# Receive.net
KiCad netlist of a schematic drawn in Altium Designer
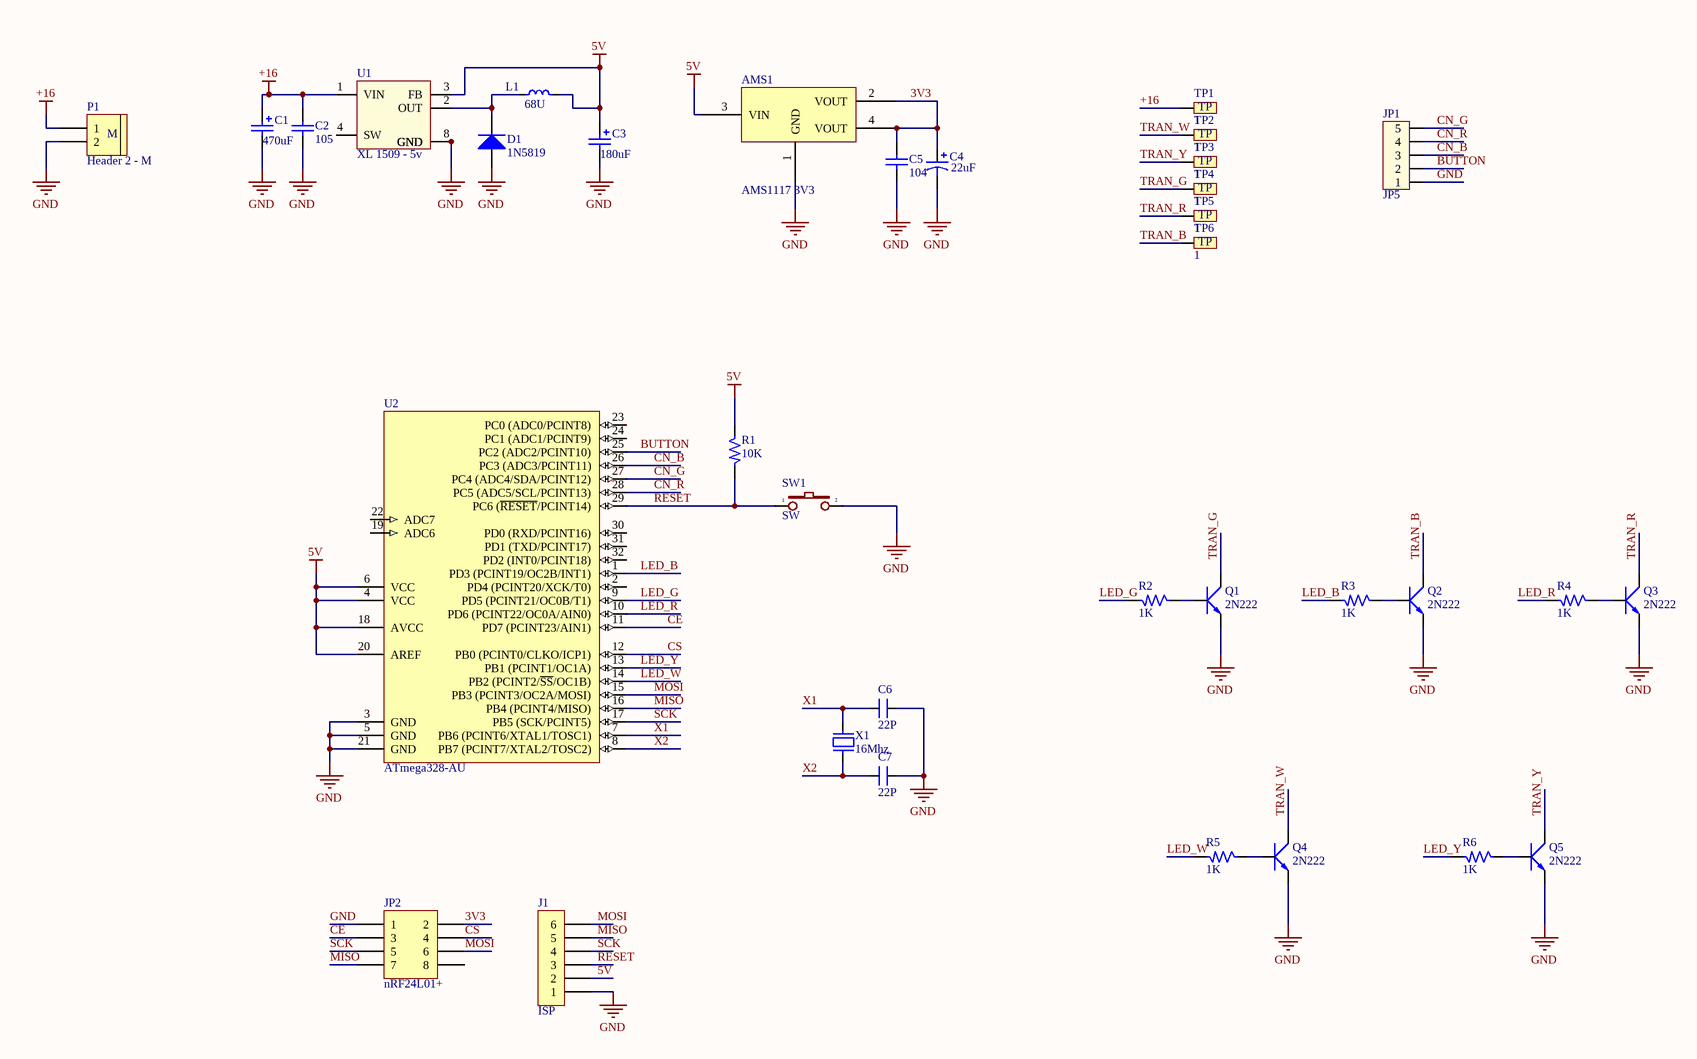
[diagram p0: Receive.SchDoc]

(export (version "E")
  (design (tool "Eeschema 10.0.6"))
  (components
    (comp (ref "AMS1")
      (value "AMS1117 3V3")
      (footprint "SOT223-4N")
      (description "AMS")
      (libsource (lib "Thu Vien Chuan") (part "AMS1117"))
    )
    (comp (ref "C1")
      (value "470uF")
      (footprint "CP2/5")
      (description "Polarized Capacitor (Surface Mount)")
      (fields (field (name "PUBLISHER") "Altium Limited"))
      (libsource (lib "Thu Vien Chuan") (part "Cap Pol3"))
    )
    (comp (ref "C2")
      (value "105")
      (footprint "Thu Vien Chuan :CN-SMD-0805")
      (libsource (lib "Thu Vien Chuan") (part "CAP 33P_0805"))
    )
    (comp (ref "C3")
      (value "180uF")
      (footprint "CP2/5")
      (description "Polarized Capacitor (Surface Mount)")
      (fields (field (name "PUBLISHER") "Altium Limited"))
      (libsource (lib "Thu Vien Chuan") (part "Cap Pol3"))
    )
    (comp (ref "C4")
      (value "22uF")
      (footprint "C5mm")
      (description "Polarized Capacitor (Axial)")
      (fields (field (name "PUBLISHER") "Altium Limited"))
      (libsource (lib "Thu Vien Chuan") (part "Cap Pol 5mm"))
    )
    (comp (ref "C5")
      (value "104")
      (footprint "Thu Vien Chuan :CN-SMD-0805")
      (libsource (lib "Thu Vien Chuan") (part "CAP 33P_0805"))
    )
    (comp (ref "C6")
      (value "22P")
      (footprint "Thu Vien Chuan :CN-SMD-0805")
      (description "Cap np  1pF - 472pF")
      (libsource (lib "Thu Vien Chuan") (part "CN1"))
    )
    (comp (ref "C7")
      (value "22P")
      (footprint "Thu Vien Chuan :CN-SMD-0805")
      (description "Cap np  1pF - 472pF")
      (libsource (lib "Thu Vien Chuan") (part "CN1"))
    )
    (comp (ref "D1")
      (value "1N5819")
      (footprint "HueNguyenLib:SS14")
      (libsource (lib "Thu Vien Chuan") (part "1N5819"))
    )
    (comp (ref "J1")
      (value "ISP")
      (footprint "Thu Vien Chuan :Header6")
      (description "JUMP DON DUC 2.54")
      (libsource (lib "Thu Vien Chuan") (part "JUMP 6"))
    )
    (comp (ref "JP1")
      (value "JP5")
      (footprint "XH2.54-5P")
      (description "Connector 5")
      (libsource (lib "Thu Vien Chuan") (part "Header 5P"))
    )
    (comp (ref "JP2")
      (value "nRF24L01+")
      (footprint "HDR2X4")
      (description "JUMP DOI DUC")
      (fields (field (name "PUBLISHER") "Altium Limited"))
      (libsource (lib "Thu Vien Chuan") (part "JUMP DOI-4"))
    )
    (comp (ref "L1")
      (value "68U")
      (footprint "HueNguyenLib:CD75")
      (description "Cuon cam")
      (libsource (lib "Thu Vien Chuan") (part "L100uH3A"))
    )
    (comp (ref "P1")
      (value "Header 2 - M")
      (footprint "Medium - Header 2")
      (description "Header, 2-Pin, Medium")
      (fields (field (name "PUBLISHER") "Altium Limited"))
      (libsource (lib "Thu Vien Chuan") (part "Header 2 - M"))
    )
    (comp (ref "Q1")
      (value "2N222")
      (footprint "Thu Vien Chuan :SOT23-231")
      (description "P 600mW, EBC")
      (libsource (lib "Thu Vien Chuan") (part "NPN_EBC"))
    )
    (comp (ref "Q2")
      (value "2N222")
      (footprint "Thu Vien Chuan :SOT23-231")
      (description "P 600mW, EBC")
      (libsource (lib "Thu Vien Chuan") (part "NPN_EBC"))
    )
    (comp (ref "Q3")
      (value "2N222")
      (footprint "Thu Vien Chuan :SOT23-231")
      (description "P 600mW, EBC")
      (libsource (lib "Thu Vien Chuan") (part "NPN_EBC"))
    )
    (comp (ref "Q4")
      (value "2N222")
      (footprint "Thu Vien Chuan :SOT23-231")
      (description "P 600mW, EBC")
      (libsource (lib "Thu Vien Chuan") (part "NPN_EBC"))
    )
    (comp (ref "Q5")
      (value "2N222")
      (footprint "Thu Vien Chuan :SOT23-231")
      (description "P 600mW, EBC")
      (libsource (lib "Thu Vien Chuan") (part "NPN_EBC"))
    )
    (comp (ref "R1")
      (value "10K")
      (footprint "Thu Vien Chuan :RES-SMD-0805")
      (description "Tro 1/4W")
      (libsource (lib "Thu Vien Chuan") (part "RES 1/4W"))
    )
    (comp (ref "R2")
      (value "1K")
      (footprint "Thu Vien Chuan :RES-SMD-0805")
      (description "Tro 1/4W")
      (libsource (lib "Thu Vien Chuan") (part "RES 1/4W"))
    )
    (comp (ref "R3")
      (value "1K")
      (footprint "Thu Vien Chuan :RES-SMD-0805")
      (description "Tro 1/4W")
      (libsource (lib "Thu Vien Chuan") (part "RES 1/4W"))
    )
    (comp (ref "R4")
      (value "1K")
      (footprint "Thu Vien Chuan :RES-SMD-0805")
      (description "Tro 1/4W")
      (libsource (lib "Thu Vien Chuan") (part "RES 1/4W"))
    )
    (comp (ref "R5")
      (value "1K")
      (footprint "Thu Vien Chuan :RES-SMD-0805")
      (description "Tro 1/4W")
      (libsource (lib "Thu Vien Chuan") (part "RES 1/4W"))
    )
    (comp (ref "R6")
      (value "1K")
      (footprint "Thu Vien Chuan :RES-SMD-0805")
      (description "Tro 1/4W")
      (libsource (lib "Thu Vien Chuan") (part "RES 1/4W"))
    )
    (comp (ref "SW1")
      (value "SW")
      (footprint "SW2")
      (description "Switch button 2 pin")
      (libsource (lib "Thu Vien Chuan") (part "SW2"))
    )
    (comp (ref "TP1")
      (value "1")
      (footprint "TP")
      (description "CONNECT 1")
      (libsource (lib "Thu Vien Chuan") (part "TP"))
    )
    (comp (ref "TP2")
      (value "1")
      (footprint "TP")
      (description "CONNECT 1")
      (libsource (lib "Thu Vien Chuan") (part "TP"))
    )
    (comp (ref "TP3")
      (value "1")
      (footprint "TP")
      (description "CONNECT 1")
      (libsource (lib "Thu Vien Chuan") (part "TP"))
    )
    (comp (ref "TP4")
      (value "1")
      (footprint "TP")
      (description "CONNECT 1")
      (libsource (lib "Thu Vien Chuan") (part "TP"))
    )
    (comp (ref "TP5")
      (value "1")
      (footprint "TP")
      (description "CONNECT 1")
      (libsource (lib "Thu Vien Chuan") (part "TP"))
    )
    (comp (ref "TP6")
      (value "1")
      (footprint "TP")
      (description "CONNECT 1")
      (libsource (lib "Thu Vien Chuan") (part "TP"))
    )
    (comp (ref "U1")
      (value "XL 1509 - 5v")
      (footprint "HueNguyenLib:XL1509 - SOIC 8")
      (description "IC HA AP 5V")
      (libsource (lib "HueNguyenLib") (part "XL 1509 - 5v"))
    )
    (comp (ref "U2")
      (value "ATmega328-AU")
      (footprint "TQFP32")
      (fields (field (name "PUBLISHER") "Altium Limited"))
      (libsource (lib "Thu Vien Chuan") (part "ATmega328-AU"))
    )
    (comp (ref "X1")
      (value "16Mhz")
      (footprint "XT2")
      (description "Crystal For all Crystal 2pin.")
      (libsource (lib "Thu Vien Chuan") (part "XT2"))
    )
  )
  (nets
    (net (code "1") (name "+16") (class "Default")
      (node (ref "C1") (pin "1") (pinfunction "1_1") (pintype "passive"))
      (node (ref "C2") (pin "2") (pinfunction "2_2") (pintype "passive"))
      (node (ref "P1") (pin "1") (pinfunction "1_1") (pintype "passive"))
      (node (ref "TP1") (pin "TP1") (pinfunction "0_TP1") (pintype "passive"))
      (node (ref "U1") (pin "1") (pinfunction "VIN_1") (pintype "passive"))
    )
    (net (code "2") (name "/3V3") (class "Default")
      (node (ref "AMS1") (pin "2") (pinfunction "VOUT_2") (pintype "passive"))
      (node (ref "AMS1") (pin "4") (pinfunction "VOUT_4") (pintype "passive"))
      (node (ref "C4") (pin "1") (pinfunction "1_1") (pintype "passive"))
      (node (ref "C5") (pin "2") (pinfunction "2_2") (pintype "passive"))
      (node (ref "JP2") (pin "2") (pinfunction "2_2") (pintype "passive"))
    )
    (net (code "3") (name "/BUTTON") (class "Default")
      (node (ref "JP1") (pin "2") (pinfunction "2_2") (pintype "passive"))
      (node (ref "U2") (pin "25") (pinfunction "PC2_(ADC2/PCINT10)_25") (pintype "bidirectional"))
    )
    (net (code "4") (name "/CE") (class "Default")
      (node (ref "JP2") (pin "3") (pinfunction "3_3") (pintype "passive"))
      (node (ref "U2") (pin "11") (pinfunction "PD7_(PCINT23/AIN1)_11") (pintype "bidirectional"))
    )
    (net (code "5") (name "/CN_B") (class "Default")
      (node (ref "JP1") (pin "3") (pinfunction "3_3") (pintype "passive"))
      (node (ref "U2") (pin "26") (pinfunction "PC3_(ADC3/PCINT11)_26") (pintype "bidirectional"))
    )
    (net (code "6") (name "/CN_G") (class "Default")
      (node (ref "JP1") (pin "5") (pinfunction "5_5") (pintype "passive"))
      (node (ref "U2") (pin "27") (pinfunction "PC4_(ADC4/SDA/PCINT12)_27") (pintype "bidirectional"))
    )
    (net (code "7") (name "/CN_R") (class "Default")
      (node (ref "JP1") (pin "4") (pinfunction "4_4") (pintype "passive"))
      (node (ref "U2") (pin "28") (pinfunction "PC5_(ADC5/SCL/PCINT13)_28") (pintype "bidirectional"))
    )
    (net (code "8") (name "/CS") (class "Default")
      (node (ref "JP2") (pin "4") (pinfunction "4_4") (pintype "passive"))
      (node (ref "U2") (pin "12") (pinfunction "PB0_(PCINT0/CLKO/ICP1)_12") (pintype "bidirectional"))
    )
    (net (code "9") (name "/LED_B") (class "Default")
      (node (ref "R3") (pin "2") (pinfunction "2_2") (pintype "passive"))
      (node (ref "U2") (pin "1") (pinfunction "PD3_(PCINT19/OC2B/INT1)_1") (pintype "bidirectional"))
    )
    (net (code "10") (name "/LED_G") (class "Default")
      (node (ref "R2") (pin "2") (pinfunction "2_2") (pintype "passive"))
      (node (ref "U2") (pin "9") (pinfunction "PD5_(PCINT21/OC0B/T1)_9") (pintype "bidirectional"))
    )
    (net (code "11") (name "/LED_R") (class "Default")
      (node (ref "R4") (pin "2") (pinfunction "2_2") (pintype "passive"))
      (node (ref "U2") (pin "10") (pinfunction "PD6_(PCINT22/OC0A/AIN0)_10") (pintype "bidirectional"))
    )
    (net (code "12") (name "/LED_W") (class "Default")
      (node (ref "R5") (pin "2") (pinfunction "2_2") (pintype "passive"))
      (node (ref "U2") (pin "14") (pinfunction "PB2_(PCINT2/~{SS}/OC1B)_14") (pintype "bidirectional"))
    )
    (net (code "13") (name "/LED_Y") (class "Default")
      (node (ref "R6") (pin "2") (pinfunction "2_2") (pintype "passive"))
      (node (ref "U2") (pin "13") (pinfunction "PB1_(PCINT1/OC1A)_13") (pintype "bidirectional"))
    )
    (net (code "14") (name "/MISO") (class "Default")
      (node (ref "J1") (pin "5") (pinfunction "5_5") (pintype "passive"))
      (node (ref "JP2") (pin "7") (pinfunction "7_7") (pintype "passive"))
      (node (ref "U2") (pin "16") (pinfunction "PB4_(PCINT4/MISO)_16") (pintype "bidirectional"))
    )
    (net (code "15") (name "/MOSI") (class "Default")
      (node (ref "J1") (pin "6") (pinfunction "6_6") (pintype "passive"))
      (node (ref "JP2") (pin "6") (pinfunction "6_6") (pintype "passive"))
      (node (ref "U2") (pin "15") (pinfunction "PB3_(PCINT3/OC2A/MOSI)_15") (pintype "bidirectional"))
    )
    (net (code "16") (name "/RESET") (class "Default")
      (node (ref "J1") (pin "3") (pinfunction "3_3") (pintype "passive"))
      (node (ref "R1") (pin "2") (pinfunction "2_2") (pintype "passive"))
      (node (ref "SW1") (pin "1") (pinfunction "1_1") (pintype "passive"))
      (node (ref "U2") (pin "29") (pinfunction "PC6_(~{RESET}/PCINT14)_29") (pintype "bidirectional"))
    )
    (net (code "17") (name "/SCK") (class "Default")
      (node (ref "J1") (pin "4") (pinfunction "4_4") (pintype "passive"))
      (node (ref "JP2") (pin "5") (pinfunction "5_5") (pintype "passive"))
      (node (ref "U2") (pin "17") (pinfunction "PB5_(SCK/PCINT5)_17") (pintype "bidirectional"))
    )
    (net (code "18") (name "/TRAN_B") (class "Default")
      (node (ref "Q2") (pin "3") (pinfunction "C_3") (pintype "passive"))
      (node (ref "TP6") (pin "TP1") (pinfunction "0_TP1") (pintype "passive"))
    )
    (net (code "19") (name "/TRAN_G") (class "Default")
      (node (ref "Q1") (pin "3") (pinfunction "C_3") (pintype "passive"))
      (node (ref "TP4") (pin "TP1") (pinfunction "0_TP1") (pintype "passive"))
    )
    (net (code "20") (name "/TRAN_R") (class "Default")
      (node (ref "Q3") (pin "3") (pinfunction "C_3") (pintype "passive"))
      (node (ref "TP5") (pin "TP1") (pinfunction "0_TP1") (pintype "passive"))
    )
    (net (code "21") (name "/TRAN_W") (class "Default")
      (node (ref "Q4") (pin "3") (pinfunction "C_3") (pintype "passive"))
      (node (ref "TP2") (pin "TP1") (pinfunction "0_TP1") (pintype "passive"))
    )
    (net (code "22") (name "/TRAN_Y") (class "Default")
      (node (ref "Q5") (pin "3") (pinfunction "C_3") (pintype "passive"))
      (node (ref "TP3") (pin "TP1") (pinfunction "0_TP1") (pintype "passive"))
    )
    (net (code "23") (name "/X1") (class "Default")
      (node (ref "C6") (pin "2") (pinfunction "2_2") (pintype "passive"))
      (node (ref "U2") (pin "7") (pinfunction "PB6_(PCINT6/XTAL1/TOSC1)_7") (pintype "bidirectional"))
      (node (ref "X1") (pin "2") (pinfunction "2_2") (pintype "passive"))
    )
    (net (code "24") (name "/X2") (class "Default")
      (node (ref "C7") (pin "2") (pinfunction "2_2") (pintype "passive"))
      (node (ref "U2") (pin "8") (pinfunction "PB7_(PCINT7/XTAL2/TOSC2)_8") (pintype "bidirectional"))
      (node (ref "X1") (pin "1") (pinfunction "1_1") (pintype "passive"))
    )
    (net (code "25") (name "5V") (class "Default")
      (node (ref "AMS1") (pin "3") (pinfunction "VIN_3") (pintype "passive"))
      (node (ref "C3") (pin "1") (pinfunction "1_1") (pintype "passive"))
      (node (ref "J1") (pin "2") (pinfunction "2_2") (pintype "passive"))
      (node (ref "L1") (pin "2") (pinfunction "2_2") (pintype "passive"))
      (node (ref "R1") (pin "1") (pinfunction "1_1") (pintype "passive"))
      (node (ref "U1") (pin "3") (pinfunction "FB_3") (pintype "passive"))
      (node (ref "U2") (pin "18") (pinfunction "AVCC_18") (pintype "power_in"))
      (node (ref "U2") (pin "20") (pinfunction "AREF_20") (pintype "passive"))
      (node (ref "U2") (pin "4") (pinfunction "VCC_4") (pintype "power_in"))
      (node (ref "U2") (pin "6") (pinfunction "VCC_6") (pintype "power_in"))
    )
    (net (code "26") (name "GND") (class "Default")
      (node (ref "AMS1") (pin "1") (pinfunction "GND_1") (pintype "passive"))
      (node (ref "C1") (pin "2") (pinfunction "2_2") (pintype "passive"))
      (node (ref "C2") (pin "1") (pinfunction "1_1") (pintype "passive"))
      (node (ref "C3") (pin "2") (pinfunction "2_2") (pintype "passive"))
      (node (ref "C4") (pin "2") (pinfunction "2_2") (pintype "passive"))
      (node (ref "C5") (pin "1") (pinfunction "1_1") (pintype "passive"))
      (node (ref "C6") (pin "1") (pinfunction "1_1") (pintype "passive"))
      (node (ref "C7") (pin "1") (pinfunction "1_1") (pintype "passive"))
      (node (ref "D1") (pin "1") (pinfunction "Anot_1") (pintype "passive"))
      (node (ref "J1") (pin "1") (pinfunction "1_1") (pintype "passive"))
      (node (ref "JP1") (pin "1") (pinfunction "1_1") (pintype "passive"))
      (node (ref "JP2") (pin "1") (pinfunction "1_1") (pintype "passive"))
      (node (ref "P1") (pin "2") (pinfunction "2_2") (pintype "passive"))
      (node (ref "Q1") (pin "1") (pinfunction "E_1") (pintype "passive"))
      (node (ref "Q2") (pin "1") (pinfunction "E_1") (pintype "passive"))
      (node (ref "Q3") (pin "1") (pinfunction "E_1") (pintype "passive"))
      (node (ref "Q4") (pin "1") (pinfunction "E_1") (pintype "passive"))
      (node (ref "Q5") (pin "1") (pinfunction "E_1") (pintype "passive"))
      (node (ref "SW1") (pin "2") (pinfunction "2_2") (pintype "passive"))
      (node (ref "U1") (pin "5") (pinfunction "GND_5") (pintype "passive"))
      (node (ref "U1") (pin "6") (pinfunction "GND_6") (pintype "passive"))
      (node (ref "U1") (pin "7") (pinfunction "GND_7") (pintype "passive"))
      (node (ref "U1") (pin "8") (pinfunction "GND_8") (pintype "passive"))
      (node (ref "U2") (pin "21") (pinfunction "GND_21") (pintype "power_in"))
      (node (ref "U2") (pin "3") (pinfunction "GND_3") (pintype "power_in"))
      (node (ref "U2") (pin "5") (pinfunction "GND_5") (pintype "power_in"))
    )
    (net (code "27") (name "Net-(D1-Katot)") (class "Default")
      (node (ref "D1") (pin "2") (pinfunction "Katot_2") (pintype "passive"))
      (node (ref "L1") (pin "1") (pinfunction "1_1") (pintype "passive"))
      (node (ref "U1") (pin "2") (pinfunction "OUT_2") (pintype "passive"))
    )
    (net (code "28") (name "Net-(Q1-B)") (class "Default")
      (node (ref "Q1") (pin "2") (pinfunction "B_2") (pintype "passive"))
      (node (ref "R2") (pin "1") (pinfunction "1_1") (pintype "passive"))
    )
    (net (code "29") (name "Net-(Q2-B)") (class "Default")
      (node (ref "Q2") (pin "2") (pinfunction "B_2") (pintype "passive"))
      (node (ref "R3") (pin "1") (pinfunction "1_1") (pintype "passive"))
    )
    (net (code "30") (name "Net-(Q3-B)") (class "Default")
      (node (ref "Q3") (pin "2") (pinfunction "B_2") (pintype "passive"))
      (node (ref "R4") (pin "1") (pinfunction "1_1") (pintype "passive"))
    )
    (net (code "31") (name "Net-(Q4-B)") (class "Default")
      (node (ref "Q4") (pin "2") (pinfunction "B_2") (pintype "passive"))
      (node (ref "R5") (pin "1") (pinfunction "1_1") (pintype "passive"))
    )
    (net (code "32") (name "Net-(Q5-B)") (class "Default")
      (node (ref "Q5") (pin "2") (pinfunction "B_2") (pintype "passive"))
      (node (ref "R6") (pin "1") (pinfunction "1_1") (pintype "passive"))
    )
    (net (code "33") (name "unconnected-(JP2-Pad8)") (class "Default")
      (node (ref "JP2") (pin "8") (pinfunction "8_8") (pintype "passive"))
    )
    (net (code "34") (name "unconnected-(U1-SW-Pad4)") (class "Default")
      (node (ref "U1") (pin "4") (pinfunction "SW_4") (pintype "passive"))
    )
    (net (code "35") (name "unconnected-(U2-ADC6-Pad19)") (class "Default")
      (node (ref "U2") (pin "19") (pinfunction "ADC6_19") (pintype "input"))
    )
    (net (code "36") (name "unconnected-(U2-ADC7-Pad22)") (class "Default")
      (node (ref "U2") (pin "22") (pinfunction "ADC7_22") (pintype "input"))
    )
    (net (code "37") (name "unconnected-(U2-PC0_(ADC0{slash}PCINT8)-Pad23)") (class "Default")
      (node (ref "U2") (pin "23") (pinfunction "PC0_(ADC0/PCINT8)_23") (pintype "bidirectional"))
    )
    (net (code "38") (name "unconnected-(U2-PC1_(ADC1{slash}PCINT9)-Pad24)") (class "Default")
      (node (ref "U2") (pin "24") (pinfunction "PC1_(ADC1/PCINT9)_24") (pintype "bidirectional"))
    )
    (net (code "39") (name "unconnected-(U2-PD0_(RXD{slash}PCINT16)-Pad30)") (class "Default")
      (node (ref "U2") (pin "30") (pinfunction "PD0_(RXD/PCINT16)_30") (pintype "bidirectional"))
    )
    (net (code "40") (name "unconnected-(U2-PD1_(TXD{slash}PCINT17)-Pad31)") (class "Default")
      (node (ref "U2") (pin "31") (pinfunction "PD1_(TXD/PCINT17)_31") (pintype "bidirectional"))
    )
    (net (code "41") (name "unconnected-(U2-PD2_(INT0{slash}PCINT18)-Pad32)") (class "Default")
      (node (ref "U2") (pin "32") (pinfunction "PD2_(INT0/PCINT18)_32") (pintype "bidirectional"))
    )
    (net (code "42") (name "unconnected-(U2-PD4_(PCINT20{slash}XCK{slash}T0)-Pad2)") (class "Default")
      (node (ref "U2") (pin "2") (pinfunction "PD4_(PCINT20/XCK/T0)_2") (pintype "bidirectional"))
    )
  )
)
